# USB-to-Serial_Converter.net
KiCad netlist of a schematic drawn in Altium Designer
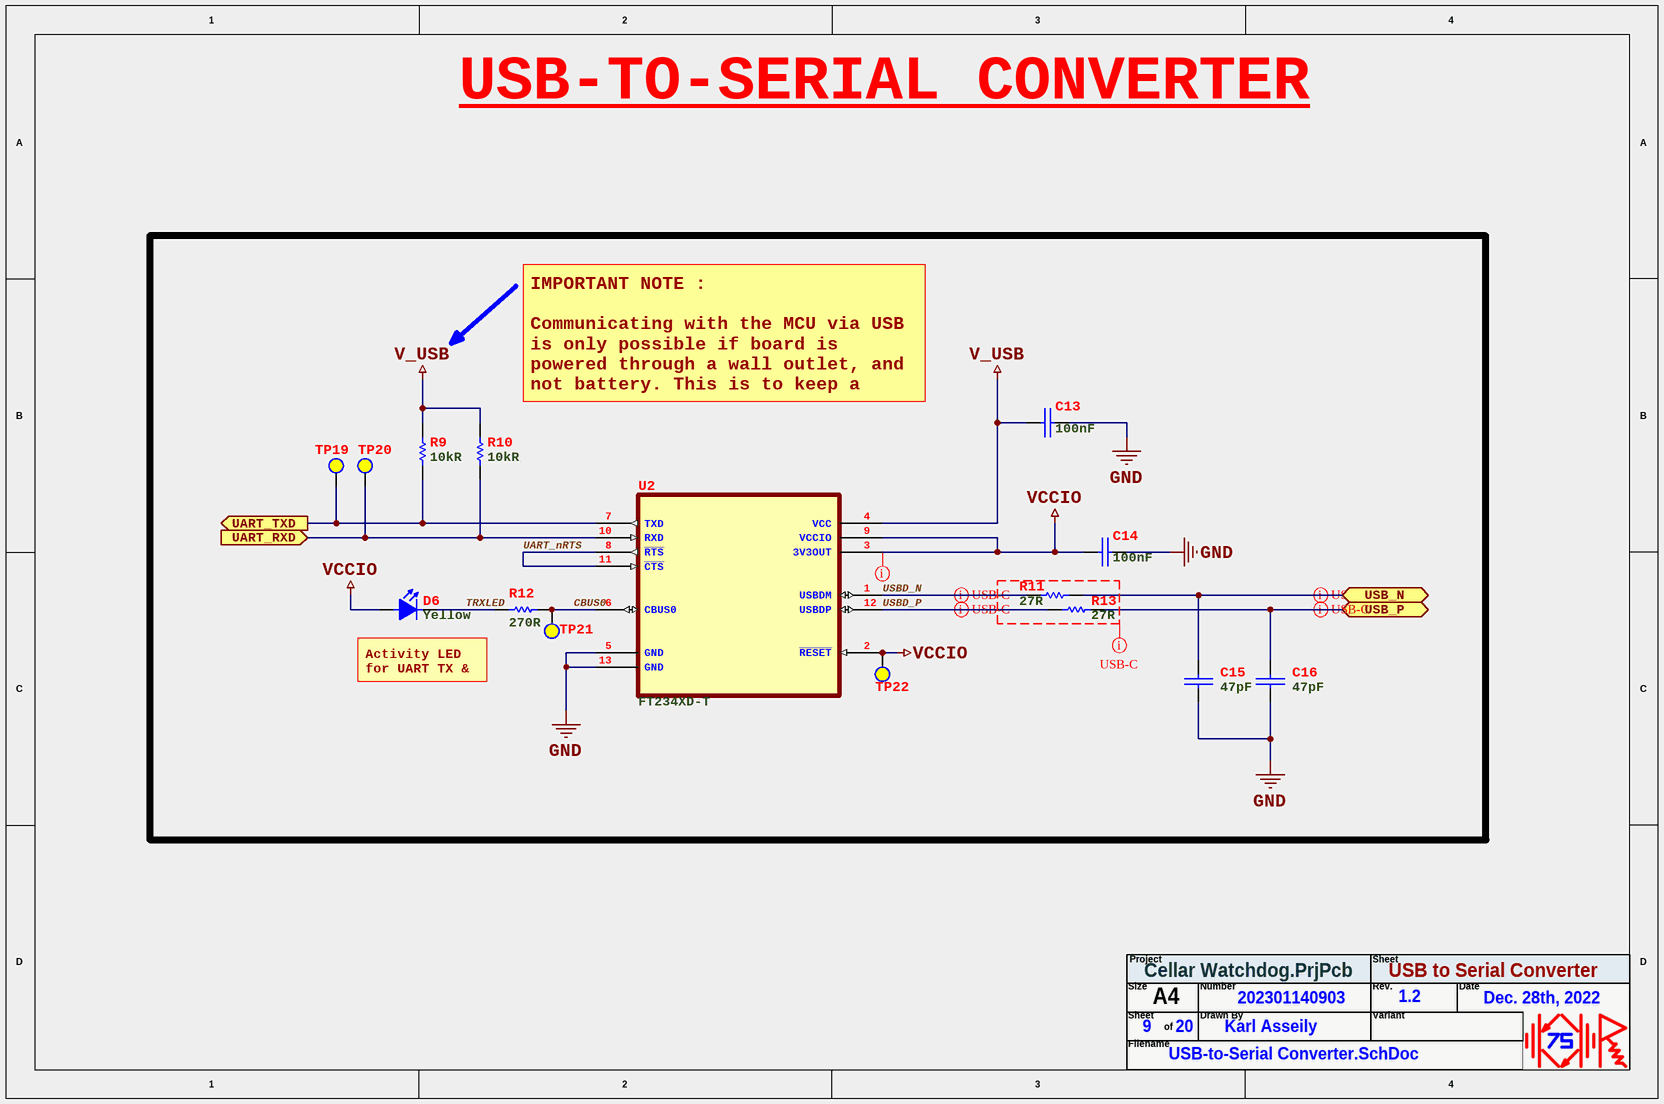
[diagram p0: USB-to-Serial Converter.SchDoc]

(export (version "E")
  (design (tool "Eeschema 10.0.6"))
  (components
    (comp (ref "C13")
      (value "100nF")
      (footprint "CAP_0603")
      (description "0.1 µF ±10% 50V Ceramic Capacitor X7R 0603 (1608 Metric)")
      (fields
        (field (name "MANUFACTURER") "Yageo")
        (field (name "MANUFACTURER PART NUMBER") "CC0603KRX7R9BB104")
      )
      (libsource (lib "Cellar Watchdog") (part "CAP_0.1uF-50V-10%_0603"))
    )
    (comp (ref "C14")
      (value "100nF")
      (footprint "CAP_0603")
      (description "0.1 µF ±10% 50V Ceramic Capacitor X7R 0603 (1608 Metric)")
      (fields
        (field (name "MANUFACTURER") "Yageo")
        (field (name "MANUFACTURER PART NUMBER") "CC0603KRX7R9BB104")
      )
      (libsource (lib "Cellar Watchdog") (part "CAP_0.1uF-50V-10%_0603"))
    )
    (comp (ref "C15")
      (value "47pF")
      (footprint "CAP_0603")
      (description "47 pF ±5% 50V Ceramic Capacitor C0G, NP0 0603 (1608 Metric)")
      (fields
        (field (name "MANUFACTURER") "Yageo Phycomp")
        (field (name "MANUFACTURER PART NUMBER") "CC0603JRNPO9BN470")
      )
      (libsource (lib "Cellar Watchdog") (part "CAP_47pf-50V-5%_0603"))
    )
    (comp (ref "C16")
      (value "47pF")
      (footprint "CAP_0603")
      (description "47 pF ±5% 50V Ceramic Capacitor C0G, NP0 0603 (1608 Metric)")
      (fields
        (field (name "MANUFACTURER") "Yageo Phycomp")
        (field (name "MANUFACTURER PART NUMBER") "CC0603JRNPO9BN470")
      )
      (libsource (lib "Cellar Watchdog") (part "CAP_47pf-50V-5%_0603"))
    )
    (comp (ref "D6")
      (value "Yellow")
      (footprint "LED_YLW_0603")
      (description "Yellow 591nm LED Indication - Discrete 2.1V 0603 (1608 Metric)")
      (fields
        (field (name "MANUFACTURER") "Vishay Lite-On")
        (field (name "MANUFACTURER PART NUMBER") "LTST-C191KSKT")
      )
      (libsource (lib "Cellar Watchdog") (part "LED_YLW-2.1V-30mA_0603"))
    )
    (comp (ref "R9")
      (value "10kR")
      (footprint "RES_0603")
      (description "10 kOhms ±1% 0.1W, 1/10W Chip Resistor 0603 (1608 Metric) Moisture Resistant Thick Film")
      (fields
        (field (name "MANUFACTURER") "Yageo")
        (field (name "MANUFACTURER PART NUMBER") "RC0603FR-0710KL")
      )
      (libsource (lib "Cellar Watchdog") (part "RES_10kR-100mW-1%_0603"))
    )
    (comp (ref "R10")
      (value "10kR")
      (footprint "RES_0603")
      (description "10 kOhms ±1% 0.1W, 1/10W Chip Resistor 0603 (1608 Metric) Moisture Resistant Thick Film")
      (fields
        (field (name "MANUFACTURER") "Yageo")
        (field (name "MANUFACTURER PART NUMBER") "RC0603FR-0710KL")
      )
      (libsource (lib "Cellar Watchdog") (part "RES_10kR-100mW-1%_0603"))
    )
    (comp (ref "R11")
      (value "27R")
      (footprint "RES_0603")
      (description "27 Ohms ±1% 0.1W, 1/10W Chip Resistor 0603 (1608 Metric) Moisture Resistant Thick Film")
      (fields
        (field (name "MANUFACTURER") "Yageo")
        (field (name "MANUFACTURER PART NUMBER") "RC0603FR-0727RL")
      )
      (libsource (lib "Cellar Watchdog") (part "RES_27R-100mW-1%_0603"))
    )
    (comp (ref "R12")
      (value "270R")
      (footprint "RES_0603")
      (description "270 Ohms ±1% 0.1W, 1/10W Chip Resistor 0603 (1608 Metric) Moisture Resistant Thick Film")
      (fields
        (field (name "MANUFACTURER") "Yageo")
        (field (name "MANUFACTURER PART NUMBER") "RC0603FR-07270RL")
      )
      (libsource (lib "Cellar Watchdog") (part "RES_270R-100mW-1%_0603"))
    )
    (comp (ref "R13")
      (value "27R")
      (footprint "RES_0603")
      (description "27 Ohms ±1% 0.1W, 1/10W Chip Resistor 0603 (1608 Metric) Moisture Resistant Thick Film")
      (fields
        (field (name "MANUFACTURER") "Yageo")
        (field (name "MANUFACTURER PART NUMBER") "RC0603FR-0727RL")
      )
      (libsource (lib "Cellar Watchdog") (part "RES_27R-100mW-1%_0603"))
    )
    (comp (ref "TP19")
      (value "UART_TXD")
      (footprint "TEST POINT HOLE")
      (description "PCB Test Point")
      (libsource (lib "Cellar Watchdog") (part "Test Point"))
    )
    (comp (ref "TP20")
      (value "UART_RXD")
      (footprint "TEST POINT HOLE")
      (description "PCB Test Point")
      (libsource (lib "Cellar Watchdog") (part "Test Point"))
    )
    (comp (ref "TP21")
      (value "CBUS0")
      (footprint "TEST POINT HOLE")
      (description "PCB Test Point")
      (libsource (lib "Cellar Watchdog") (part "Test Point"))
    )
    (comp (ref "TP22")
      (value "VCCIO")
      (footprint "TEST POINT HOLE")
      (description "PCB Test Point")
      (libsource (lib "Cellar Watchdog") (part "Test Point"))
    )
    (comp (ref "U2")
      (value "FT234XD-T")
      (footprint "IC_SON45P300X300X80-13N")
      (description "USB Bridge, USB to UART USB 2.0 UART Interface 12-DFN (3x3)")
      (fields (field (name "MANUFACTURER") "FTDI"))
      (libsource (lib "Cellar Watchdog") (part "IC_FT234XD-T"))
    )
  )
  (nets
    (net (code "1") (name "/CBUS0") (class "Default")
      (node (ref "R12") (pin "2") (pinfunction "2_2") (pintype "passive"))
      (node (ref "TP21") (pin "TP") (pinfunction "TP_TP") (pintype "passive"))
      (node (ref "U2") (pin "6") (pinfunction "CBUS0_6") (pintype "bidirectional"))
    )
    (net (code "2") (name "/TRXLED") (class "Default")
      (node (ref "D6") (pin "2") (pinfunction "K_2") (pintype "passive"))
      (node (ref "R12") (pin "1") (pinfunction "1_1") (pintype "passive"))
    )
    (net (code "3") (name "/UART_RXD") (class "Default")
      (node (ref "R10") (pin "1") (pinfunction "1_1") (pintype "passive"))
      (node (ref "TP20") (pin "TP") (pinfunction "TP_TP") (pintype "passive"))
      (node (ref "U2") (pin "10") (pinfunction "RXD_10") (pintype "input"))
    )
    (net (code "4") (name "/UART_TXD") (class "Default")
      (node (ref "R9") (pin "1") (pinfunction "1_1") (pintype "passive"))
      (node (ref "TP19") (pin "TP") (pinfunction "TP_TP") (pintype "passive"))
      (node (ref "U2") (pin "7") (pinfunction "TXD_7") (pintype "output"))
    )
    (net (code "5") (name "/UART_nRTS") (class "Default")
      (node (ref "U2") (pin "11") (pinfunction "CTS_11") (pintype "input"))
      (node (ref "U2") (pin "8") (pinfunction "RTS_8") (pintype "output"))
    )
    (net (code "6") (name "/USBD_N") (class "Default")
      (node (ref "R11") (pin "1") (pinfunction "1_1") (pintype "passive"))
      (node (ref "U2") (pin "1") (pinfunction "USBDM_1") (pintype "bidirectional"))
    )
    (net (code "7") (name "/USBD_P") (class "Default")
      (node (ref "R13") (pin "1") (pinfunction "1_1") (pintype "passive"))
      (node (ref "U2") (pin "12") (pinfunction "USBDP_12") (pintype "bidirectional"))
    )
    (net (code "8") (name "/USB_N") (class "Default")
      (node (ref "C15") (pin "1") (pinfunction "1_1") (pintype "passive"))
      (node (ref "R11") (pin "2") (pinfunction "2_2") (pintype "passive"))
    )
    (net (code "9") (name "/USB_P") (class "Default")
      (node (ref "C16") (pin "1") (pinfunction "1_1") (pintype "passive"))
      (node (ref "R13") (pin "2") (pinfunction "2_2") (pintype "passive"))
    )
    (net (code "10") (name "GND") (class "Default")
      (node (ref "C13") (pin "2") (pinfunction "2_2") (pintype "passive"))
      (node (ref "C14") (pin "2") (pinfunction "2_2") (pintype "passive"))
      (node (ref "C15") (pin "2") (pinfunction "2_2") (pintype "passive"))
      (node (ref "C16") (pin "2") (pinfunction "2_2") (pintype "passive"))
      (node (ref "U2") (pin "13") (pinfunction "GND_13") (pintype "power_in"))
      (node (ref "U2") (pin "5") (pinfunction "GND_5") (pintype "power_in"))
    )
    (net (code "11") (name "VCCIO") (class "Default")
      (node (ref "C14") (pin "1") (pinfunction "1_1") (pintype "passive"))
      (node (ref "D6") (pin "1") (pinfunction "A_1") (pintype "passive"))
      (node (ref "TP22") (pin "TP") (pinfunction "TP_TP") (pintype "passive"))
      (node (ref "U2") (pin "2") (pinfunction "RESET_2") (pintype "input"))
      (node (ref "U2") (pin "3") (pinfunction "3V3OUT_3") (pintype "power_in"))
      (node (ref "U2") (pin "9") (pinfunction "VCCIO_9") (pintype "power_in"))
    )
    (net (code "12") (name "V_USB") (class "Default")
      (node (ref "C13") (pin "1") (pinfunction "1_1") (pintype "passive"))
      (node (ref "R10") (pin "2") (pinfunction "2_2") (pintype "passive"))
      (node (ref "R9") (pin "2") (pinfunction "2_2") (pintype "passive"))
      (node (ref "U2") (pin "4") (pinfunction "VCC_4") (pintype "power_in"))
    )
  )
)
